# LM317_protected.net
KiCad netlist of a schematic drawn in EAGLE
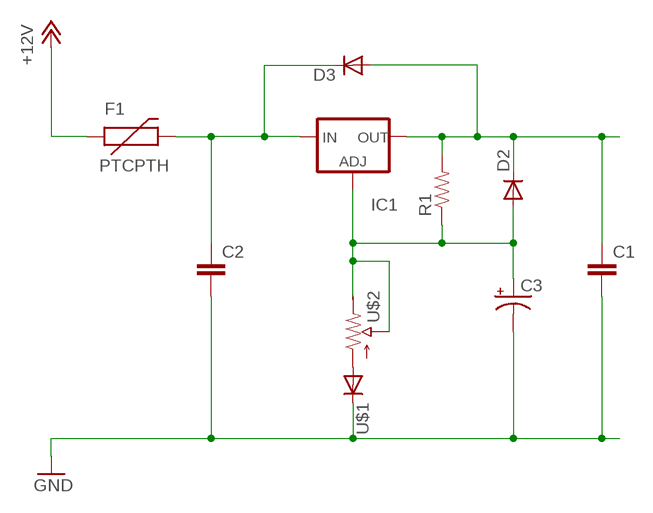
[diagram p0: schematic, sheet 1]

(export (version "E")
  (design (tool "Eeschema 10.0.6"))
  (components
    (comp (ref "C1")
      (value "CAPKIT")
      (footprint "eagle-import:CAP-PTH-SMALL-KIT")
      (libsource (lib "eagle-import") (part "CAPKIT"))
    )
    (comp (ref "C2")
      (value "CAPKIT")
      (footprint "eagle-import:CAP-PTH-SMALL-KIT")
      (libsource (lib "eagle-import") (part "CAPKIT"))
    )
    (comp (ref "C3")
      (value "CAP_POLPTH2")
      (footprint "eagle-import:CPOL-RADIAL-10UF-25V")
      (libsource (lib "eagle-import") (part "CAP_POLPTH2"))
    )
    (comp (ref "D2")
      (value "DIODEPTH")
      (footprint "eagle-import:DIODE-1N4001")
      (libsource (lib "eagle-import") (part "DIODEPTH"))
    )
    (comp (ref "D3")
      (value "DIODEPTH")
      (footprint "eagle-import:DIODE-1N4001")
      (libsource (lib "eagle-import") (part "DIODEPTH"))
    )
    (comp (ref "F1")
      (value "PTCPTH")
      (footprint "eagle-import:PTC")
      (libsource (lib "eagle-import") (part "PTCPTH"))
    )
    (comp (ref "IC1")
      (value "LM337TS")
      (footprint "eagle-import:337TS")
      (libsource (lib "eagle-import") (part "LM337TS"))
    )
    (comp (ref "R1")
      (value "RESISTORAXIAL-0.3")
      (footprint "eagle-import:AXIAL-0.3")
      (libsource (lib "eagle-import") (part "RESISTORAXIAL-0.3"))
    )
    (comp (ref "U$1")
      (value "DIODE1N4148")
      (footprint "eagle-import:DIODE-1N4148")
      (libsource (lib "eagle-import") (part "DIODE1N4148"))
    )
    (comp (ref "U$2")
      (value "POT100K_3362U")
      (footprint "eagle-import:3362U")
      (libsource (lib "eagle-import") (part "POT100K_3362U"))
    )
  )
  (nets
    (net (code "1") (name "+12V") (class "Default")
      (node (ref "F1") (pin "P$1") (pinfunction "1_P$1") (pintype "bidirectional"))
    )
    (net (code "2") (name "GND") (class "Default")
      (node (ref "C1") (pin "2") (pinfunction "2_2") (pintype "passive"))
      (node (ref "C2") (pin "2") (pinfunction "2_2") (pintype "passive"))
      (node (ref "C3") (pin "2") (pinfunction "-_2") (pintype "passive"))
      (node (ref "U$1") (pin "C") (pinfunction "C_C") (pintype "passive"))
    )
    (net (code "3") (name "Net-(C3-+)") (class "Default")
      (node (ref "C3") (pin "1") (pinfunction "+_1") (pintype "passive"))
      (node (ref "D2") (pin "A") (pinfunction "A_A") (pintype "passive"))
      (node (ref "IC1") (pin "1") (pinfunction "ADJ_1") (pintype "input"))
      (node (ref "R1") (pin "P$1") (pinfunction "1_P$1") (pintype "passive"))
      (node (ref "U$2") (pin "P$1") (pinfunction "E_P$1") (pintype "passive"))
      (node (ref "U$2") (pin "P$2") (pinfunction "S_P$2") (pintype "passive"))
    )
    (net (code "4") (name "Net-(F1-2)") (class "Default")
      (node (ref "C2") (pin "1") (pinfunction "1_1") (pintype "passive"))
      (node (ref "D3") (pin "C") (pinfunction "C_C") (pintype "passive"))
      (node (ref "F1") (pin "P$2") (pinfunction "2_P$2") (pintype "bidirectional"))
      (node (ref "IC1") (pin "2") (pinfunction "IN_2") (pintype "input"))
    )
    (net (code "5") (name "Net-(IC1-OUT)") (class "Default")
      (node (ref "C1") (pin "1") (pinfunction "1_1") (pintype "passive"))
      (node (ref "D2") (pin "C") (pinfunction "C_C") (pintype "passive"))
      (node (ref "D3") (pin "A") (pinfunction "A_A") (pintype "passive"))
      (node (ref "IC1") (pin "3") (pinfunction "OUT_3") (pintype "passive"))
      (node (ref "R1") (pin "P$2") (pinfunction "2_P$2") (pintype "passive"))
    )
    (net (code "6") (name "Net-(U$2-A)") (class "Default")
      (node (ref "U$1") (pin "A") (pinfunction "A_A") (pintype "passive"))
      (node (ref "U$2") (pin "P$3") (pinfunction "A_P$3") (pintype "passive"))
    )
  )
)
